# blinkenrocket_cr2032.net
KiCad netlist of a schematic drawn in EAGLE
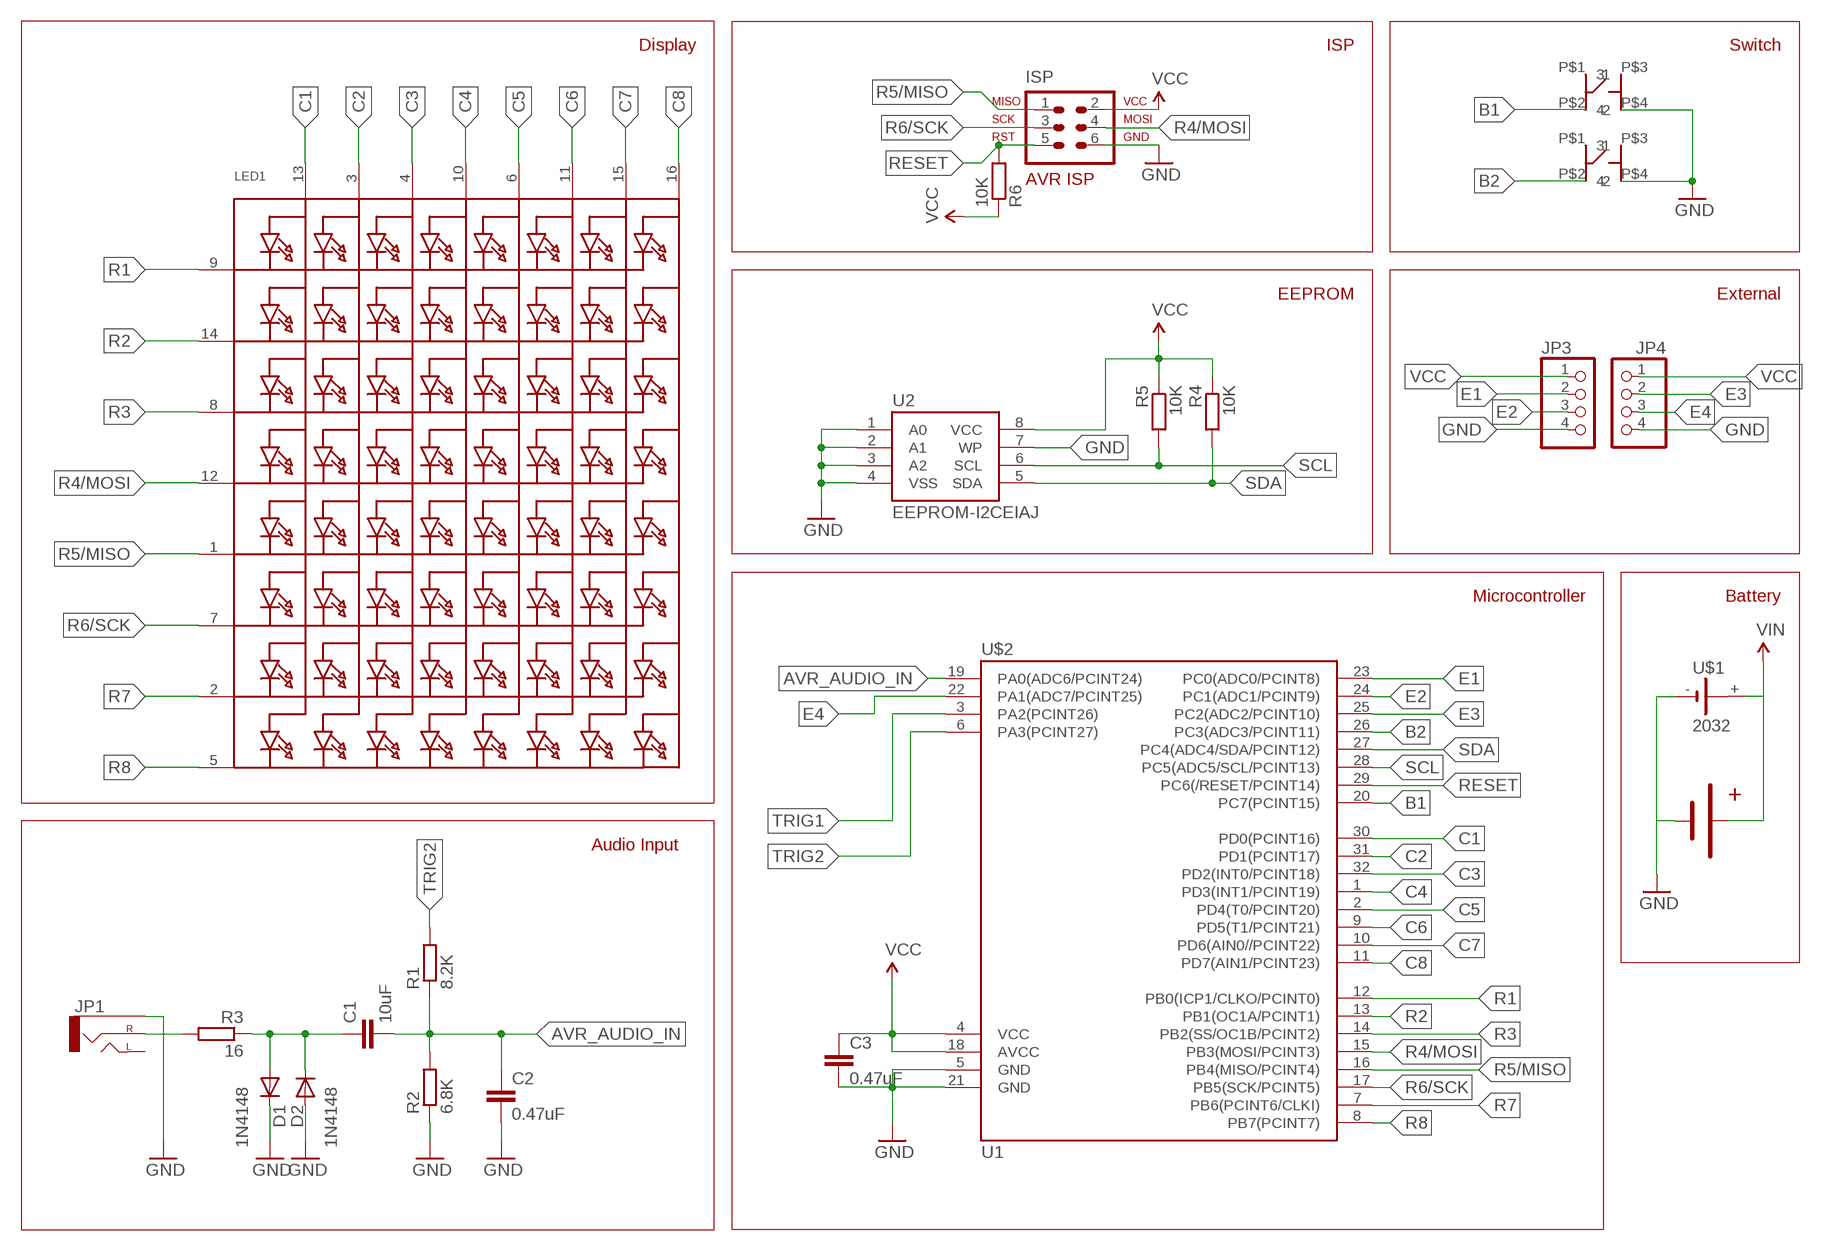
[diagram p0: schematic, sheet 1]

(export (version "E")
  (design (tool "Eeschema 10.0.6"))
  (components
    (comp (ref "C1")
      (value "10uF")
      (footprint "eagle-import:C1206")
      (libsource (lib "eagle-import") (part "C-EUC1206"))
    )
    (comp (ref "C2")
      (value "0.47uF")
      (footprint "eagle-import:C1206")
      (libsource (lib "eagle-import") (part "C-EUC1206"))
    )
    (comp (ref "C3")
      (value "0.47uF")
      (footprint "eagle-import:C1206")
      (libsource (lib "eagle-import") (part "C-EUC1206"))
    )
    (comp (ref "D1")
      (value "1N4148")
      (footprint "eagle-import:SOD3718X135N")
      (libsource (lib "eagle-import") (part "DIODE_SOD-123"))
    )
    (comp (ref "D2")
      (value "1N4148")
      (footprint "eagle-import:SOD3718X135N")
      (libsource (lib "eagle-import") (part "DIODE_SOD-123"))
    )
    (comp (ref "ISP")
      (value "AVR-ISP-6VERT")
      (footprint "eagle-import:AVR-ISP-6")
      (libsource (lib "eagle-import") (part "AVR-ISP-6VERT"))
    )
    (comp (ref "JP1")
      (value "AUDIO-JACKPTH")
      (footprint "eagle-import:AUDIO-JACK")
      (libsource (lib "eagle-import") (part "AUDIO-JACKPTH"))
    )
    (comp (ref "JP3")
      (value "PINHD-1X04_2.54-S")
      (footprint "eagle-import:1X04-S")
      (libsource (lib "eagle-import") (part "PINHD-1X04_2.54-S"))
    )
    (comp (ref "JP4")
      (value "PINHD-1X04_2.54-S")
      (footprint "eagle-import:1X04-S")
      (libsource (lib "eagle-import") (part "PINHD-1X04_2.54-S"))
    )
    (comp (ref "LED1")
      (value "SEGMENT_8X8_ROWCATHODEM12A881UR")
      (footprint "eagle-import:SEGMENT_BL-M12A881UR")
      (libsource (lib "eagle-import") (part "SEGMENT_8X8_ROWCATHODEM12A881UR"))
    )
    (comp (ref "R1")
      (value "8.2K")
      (footprint "eagle-import:R1206")
      (libsource (lib "eagle-import") (part "R-EU_R1206"))
    )
    (comp (ref "R2")
      (value "6.8K")
      (footprint "eagle-import:R1206")
      (libsource (lib "eagle-import") (part "R-EU_R1206"))
    )
    (comp (ref "R3")
      (value "16")
      (footprint "eagle-import:R1206")
      (libsource (lib "eagle-import") (part "R-EU_R1206"))
    )
    (comp (ref "R4")
      (value "10K")
      (footprint "eagle-import:R1206")
      (libsource (lib "eagle-import") (part "R-EU_R1206"))
    )
    (comp (ref "R5")
      (value "10K")
      (footprint "eagle-import:R1206")
      (libsource (lib "eagle-import") (part "R-EU_R1206"))
    )
    (comp (ref "R6")
      (value "10K")
      (footprint "eagle-import:R1206")
      (libsource (lib "eagle-import") (part "R-EU_R1206"))
    )
    (comp (ref "SW1")
      (value "SWITCH-4POMRON-6-6-SWITCH")
      (footprint "eagle-import:4P-OMRON-6-6-SWITCH")
      (libsource (lib "eagle-import") (part "SWITCH-4POMRON-6-6-SWITCH"))
    )
    (comp (ref "SW2")
      (value "SWITCH-4POMRON-6-6-SWITCH")
      (footprint "eagle-import:4P-OMRON-6-6-SWITCH")
      (libsource (lib "eagle-import") (part "SWITCH-4POMRON-6-6-SWITCH"))
    )
    (comp (ref "U$1")
      (value "2032")
      (footprint "eagle-import:KZH20SMD")
      (libsource (lib "eagle-import") (part "2032"))
    )
    (comp (ref "U$2")
      (value "U1")
      (footprint "eagle-import:TQFP32-08")
      (libsource (lib "eagle-import") (part "TINY48/88B"))
    )
    (comp (ref "U$3")
      (value "BATTERYPAD")
      (footprint "eagle-import:BATTERYPAD")
      (libsource (lib "eagle-import") (part "BATTERYPAD"))
    )
    (comp (ref "U2")
      (value "EEPROM-I2CEIAJ")
      (footprint "eagle-import:SO08-EIAJ")
      (libsource (lib "eagle-import") (part "EEPROM-I2CEIAJ"))
    )
  )
  (nets
    (net (code "1") (name "AVR_AUDIO_IN") (class "Default")
      (node (ref "C1") (pin "2") (pinfunction "2_2") (pintype "passive"))
      (node (ref "C2") (pin "1") (pinfunction "1_1") (pintype "passive"))
      (node (ref "R1") (pin "1") (pinfunction "1_1") (pintype "passive"))
      (node (ref "R2") (pin "2") (pinfunction "2_2") (pintype "passive"))
      (node (ref "U$2") (pin "19") (pinfunction "PA0(ADC6/PCINT24)_19") (pintype "bidirectional"))
    )
    (net (code "2") (name "B1") (class "Default")
      (node (ref "SW2") (pin "P$2") (pinfunction "2_P$2") (pintype "bidirectional"))
      (node (ref "U$2") (pin "20") (pinfunction "PC7(PCINT15)_20") (pintype "bidirectional"))
    )
    (net (code "3") (name "B2") (class "Default")
      (node (ref "SW1") (pin "P$2") (pinfunction "2_P$2") (pintype "bidirectional"))
      (node (ref "U$2") (pin "26") (pinfunction "PC3(ADC3/PCINT11)_26") (pintype "bidirectional"))
    )
    (net (code "4") (name "C1") (class "Default")
      (node (ref "LED1") (pin "13") (pinfunction "A1_13") (pintype "bidirectional"))
      (node (ref "U$2") (pin "30") (pinfunction "PD0(PCINT16)_30") (pintype "bidirectional"))
    )
    (net (code "5") (name "C2") (class "Default")
      (node (ref "LED1") (pin "3") (pinfunction "A2_3") (pintype "bidirectional"))
      (node (ref "U$2") (pin "31") (pinfunction "PD1(PCINT17)_31") (pintype "bidirectional"))
    )
    (net (code "6") (name "C3") (class "Default")
      (node (ref "LED1") (pin "4") (pinfunction "A3_4") (pintype "bidirectional"))
      (node (ref "U$2") (pin "32") (pinfunction "PD2(INT0/PCINT18)_32") (pintype "bidirectional"))
    )
    (net (code "7") (name "C4") (class "Default")
      (node (ref "LED1") (pin "10") (pinfunction "A4_10") (pintype "bidirectional"))
      (node (ref "U$2") (pin "1") (pinfunction "PD3(INT1/PCINT19)_1") (pintype "bidirectional"))
    )
    (net (code "8") (name "C5") (class "Default")
      (node (ref "LED1") (pin "6") (pinfunction "A5_6") (pintype "bidirectional"))
      (node (ref "U$2") (pin "2") (pinfunction "PD4(T0/PCINT20)_2") (pintype "bidirectional"))
    )
    (net (code "9") (name "C6") (class "Default")
      (node (ref "LED1") (pin "11") (pinfunction "A6_11") (pintype "bidirectional"))
      (node (ref "U$2") (pin "9") (pinfunction "PD5(T1/PCINT21)_9") (pintype "bidirectional"))
    )
    (net (code "10") (name "C7") (class "Default")
      (node (ref "LED1") (pin "15") (pinfunction "A7_15") (pintype "bidirectional"))
      (node (ref "U$2") (pin "10") (pinfunction "PD6(AIN0//PCINT22)_10") (pintype "bidirectional"))
    )
    (net (code "11") (name "C8") (class "Default")
      (node (ref "LED1") (pin "16") (pinfunction "A8_16") (pintype "bidirectional"))
      (node (ref "U$2") (pin "11") (pinfunction "PD7(AIN1/PCINT23)_11") (pintype "bidirectional"))
    )
    (net (code "12") (name "E1") (class "Default")
      (node (ref "JP3") (pin "2") (pinfunction "2_2") (pintype "passive"))
      (node (ref "U$2") (pin "23") (pinfunction "PC0(ADC0/PCINT8)_23") (pintype "bidirectional"))
    )
    (net (code "13") (name "E2") (class "Default")
      (node (ref "JP3") (pin "3") (pinfunction "3_3") (pintype "passive"))
      (node (ref "U$2") (pin "24") (pinfunction "PC1(ADC1/PCINT9)_24") (pintype "bidirectional"))
    )
    (net (code "14") (name "E3") (class "Default")
      (node (ref "JP4") (pin "2") (pinfunction "2_2") (pintype "passive"))
      (node (ref "U$2") (pin "25") (pinfunction "PC2(ADC2/PCINT10)_25") (pintype "bidirectional"))
    )
    (net (code "15") (name "E4") (class "Default")
      (node (ref "JP4") (pin "3") (pinfunction "3_3") (pintype "passive"))
      (node (ref "U$2") (pin "22") (pinfunction "PA1(ADC7/PCINT25)_22") (pintype "bidirectional"))
    )
    (net (code "16") (name "GND") (class "Default")
      (node (ref "C2") (pin "2") (pinfunction "2_2") (pintype "passive"))
      (node (ref "C3") (pin "2") (pinfunction "2_2") (pintype "passive"))
      (node (ref "D1") (pin "K") (pinfunction "K_K") (pintype "passive"))
      (node (ref "D2") (pin "A") (pinfunction "A_A") (pintype "passive"))
      (node (ref "ISP") (pin "6") (pinfunction "6_6") (pintype "passive"))
      (node (ref "JP1") (pin "SLEEVE") (pinfunction "SLEEVE_SLEEVE") (pintype "bidirectional"))
      (node (ref "JP3") (pin "4") (pinfunction "4_4") (pintype "passive"))
      (node (ref "JP4") (pin "4") (pinfunction "4_4") (pintype "passive"))
      (node (ref "R2") (pin "1") (pinfunction "1_1") (pintype "passive"))
      (node (ref "SW1") (pin "P$4") (pinfunction "4_P$4") (pintype "bidirectional"))
      (node (ref "SW2") (pin "P$4") (pinfunction "4_P$4") (pintype "bidirectional"))
      (node (ref "U$1") (pin "-") (pinfunction "-_-") (pintype "passive"))
      (node (ref "U$2") (pin "21") (pinfunction "GND_21") (pintype "power_in"))
      (node (ref "U$2") (pin "5") (pinfunction "GND_5") (pintype "power_in"))
      (node (ref "U$3") (pin "-VE") (pinfunction "-VE_-VE") (pintype "power_in"))
      (node (ref "U2") (pin "1") (pinfunction "A0_1") (pintype "bidirectional"))
      (node (ref "U2") (pin "2") (pinfunction "A1_2") (pintype "bidirectional"))
      (node (ref "U2") (pin "3") (pinfunction "A2_3") (pintype "bidirectional"))
      (node (ref "U2") (pin "4") (pinfunction "VSS_4") (pintype "power_in"))
      (node (ref "U2") (pin "7") (pinfunction "WP_7") (pintype "bidirectional"))
    )
    (net (code "17") (name "Net-(C1-Pad1)") (class "Default")
      (node (ref "C1") (pin "1") (pinfunction "1_1") (pintype "passive"))
      (node (ref "D1") (pin "A") (pinfunction "A_A") (pintype "passive"))
      (node (ref "D2") (pin "K") (pinfunction "K_K") (pintype "passive"))
      (node (ref "R3") (pin "1") (pinfunction "1_1") (pintype "passive"))
    )
    (net (code "18") (name "Net-(JP1-RIGHT)") (class "Default")
      (node (ref "JP1") (pin "RING") (pinfunction "RIGHT_RING") (pintype "bidirectional"))
      (node (ref "R3") (pin "2") (pinfunction "2_2") (pintype "passive"))
    )
    (net (code "19") (name "R1") (class "Default")
      (node (ref "LED1") (pin "9") (pinfunction "K1_9") (pintype "bidirectional"))
      (node (ref "U$2") (pin "12") (pinfunction "PB0(ICP1/CLKO/PCINT0)_12") (pintype "bidirectional"))
    )
    (net (code "20") (name "R2") (class "Default")
      (node (ref "LED1") (pin "14") (pinfunction "K2_14") (pintype "bidirectional"))
      (node (ref "U$2") (pin "13") (pinfunction "PB1(OC1A/PCINT1)_13") (pintype "bidirectional"))
    )
    (net (code "21") (name "R3") (class "Default")
      (node (ref "LED1") (pin "8") (pinfunction "K3_8") (pintype "bidirectional"))
      (node (ref "U$2") (pin "14") (pinfunction "PB2(SS/OC1B/PCINT2)_14") (pintype "bidirectional"))
    )
    (net (code "22") (name "R4{slash}MOSI") (class "Default")
      (node (ref "ISP") (pin "4") (pinfunction "4_4") (pintype "passive"))
      (node (ref "LED1") (pin "12") (pinfunction "K4_12") (pintype "bidirectional"))
      (node (ref "U$2") (pin "15") (pinfunction "PB3(MOSI/PCINT3)_15") (pintype "bidirectional"))
    )
    (net (code "23") (name "R5{slash}MISO") (class "Default")
      (node (ref "ISP") (pin "1") (pinfunction "1_1") (pintype "passive"))
      (node (ref "LED1") (pin "1") (pinfunction "K5_1") (pintype "bidirectional"))
      (node (ref "U$2") (pin "16") (pinfunction "PB4(MISO/PCINT4)_16") (pintype "bidirectional"))
    )
    (net (code "24") (name "R6{slash}SCK") (class "Default")
      (node (ref "ISP") (pin "3") (pinfunction "3_3") (pintype "passive"))
      (node (ref "LED1") (pin "7") (pinfunction "K6_7") (pintype "bidirectional"))
      (node (ref "U$2") (pin "17") (pinfunction "PB5(SCK/PCINT5)_17") (pintype "bidirectional"))
    )
    (net (code "25") (name "R7") (class "Default")
      (node (ref "LED1") (pin "2") (pinfunction "K7_2") (pintype "bidirectional"))
      (node (ref "U$2") (pin "7") (pinfunction "PB6(PCINT6/CLKI)_7") (pintype "bidirectional"))
    )
    (net (code "26") (name "R8") (class "Default")
      (node (ref "LED1") (pin "5") (pinfunction "K8_5") (pintype "bidirectional"))
      (node (ref "U$2") (pin "8") (pinfunction "PB7(PCINT7)_8") (pintype "bidirectional"))
    )
    (net (code "27") (name "RESET") (class "Default")
      (node (ref "ISP") (pin "5") (pinfunction "5_5") (pintype "passive"))
      (node (ref "R6") (pin "2") (pinfunction "2_2") (pintype "passive"))
      (node (ref "U$2") (pin "29") (pinfunction "PC6(/RESET/PCINT14)_29") (pintype "bidirectional"))
    )
    (net (code "28") (name "SCL") (class "Default")
      (node (ref "R5") (pin "2") (pinfunction "2_2") (pintype "passive"))
      (node (ref "U$2") (pin "28") (pinfunction "PC5(ADC5/SCL/PCINT13)_28") (pintype "bidirectional"))
      (node (ref "U2") (pin "6") (pinfunction "SCL_6") (pintype "bidirectional"))
    )
    (net (code "29") (name "SDA") (class "Default")
      (node (ref "R4") (pin "2") (pinfunction "2_2") (pintype "passive"))
      (node (ref "U$2") (pin "27") (pinfunction "PC4(ADC4/SDA/PCINT12)_27") (pintype "bidirectional"))
      (node (ref "U2") (pin "5") (pinfunction "SDA_5") (pintype "bidirectional"))
    )
    (net (code "30") (name "TRIG1") (class "Default")
      (node (ref "U$2") (pin "3") (pinfunction "PA2(PCINT26)_3") (pintype "bidirectional"))
    )
    (net (code "31") (name "TRIG2") (class "Default")
      (node (ref "R1") (pin "2") (pinfunction "2_2") (pintype "passive"))
      (node (ref "U$2") (pin "6") (pinfunction "PA3(PCINT27)_6") (pintype "bidirectional"))
    )
    (net (code "32") (name "VCC") (class "Default")
      (node (ref "C3") (pin "1") (pinfunction "1_1") (pintype "passive"))
      (node (ref "ISP") (pin "2") (pinfunction "2_2") (pintype "passive"))
      (node (ref "JP3") (pin "1") (pinfunction "1_1") (pintype "passive"))
      (node (ref "JP4") (pin "1") (pinfunction "1_1") (pintype "passive"))
      (node (ref "R4") (pin "1") (pinfunction "1_1") (pintype "passive"))
      (node (ref "R5") (pin "1") (pinfunction "1_1") (pintype "passive"))
      (node (ref "R6") (pin "1") (pinfunction "1_1") (pintype "passive"))
      (node (ref "U$1") (pin "+") (pinfunction "+_+") (pintype "passive"))
      (node (ref "U$2") (pin "18") (pinfunction "AVCC_18") (pintype "passive"))
      (node (ref "U$2") (pin "4") (pinfunction "VCC_4") (pintype "power_in"))
      (node (ref "U$3") (pin "+VE") (pinfunction "+VE_+VE") (pintype "power_in"))
      (node (ref "U2") (pin "8") (pinfunction "VCC_8") (pintype "power_in"))
    )
    (net (code "33") (name "unconnected-(JP1-LEFT-PadTIP)") (class "Default")
      (node (ref "JP1") (pin "TIP") (pinfunction "LEFT_TIP") (pintype "bidirectional"))
    )
    (net (code "34") (name "unconnected-(SW1-1-PadP$1)") (class "Default")
      (node (ref "SW1") (pin "P$1") (pinfunction "1_P$1") (pintype "bidirectional"))
    )
    (net (code "35") (name "unconnected-(SW1-3-PadP$3)") (class "Default")
      (node (ref "SW1") (pin "P$3") (pinfunction "3_P$3") (pintype "bidirectional"))
    )
    (net (code "36") (name "unconnected-(SW2-1-PadP$1)") (class "Default")
      (node (ref "SW2") (pin "P$1") (pinfunction "1_P$1") (pintype "bidirectional"))
    )
    (net (code "37") (name "unconnected-(SW2-3-PadP$3)") (class "Default")
      (node (ref "SW2") (pin "P$3") (pinfunction "3_P$3") (pintype "bidirectional"))
    )
  )
)
